# IoT_Greenhouse_V1_0_A_-_Inputs.net
KiCad netlist of a schematic drawn in Altium Designer
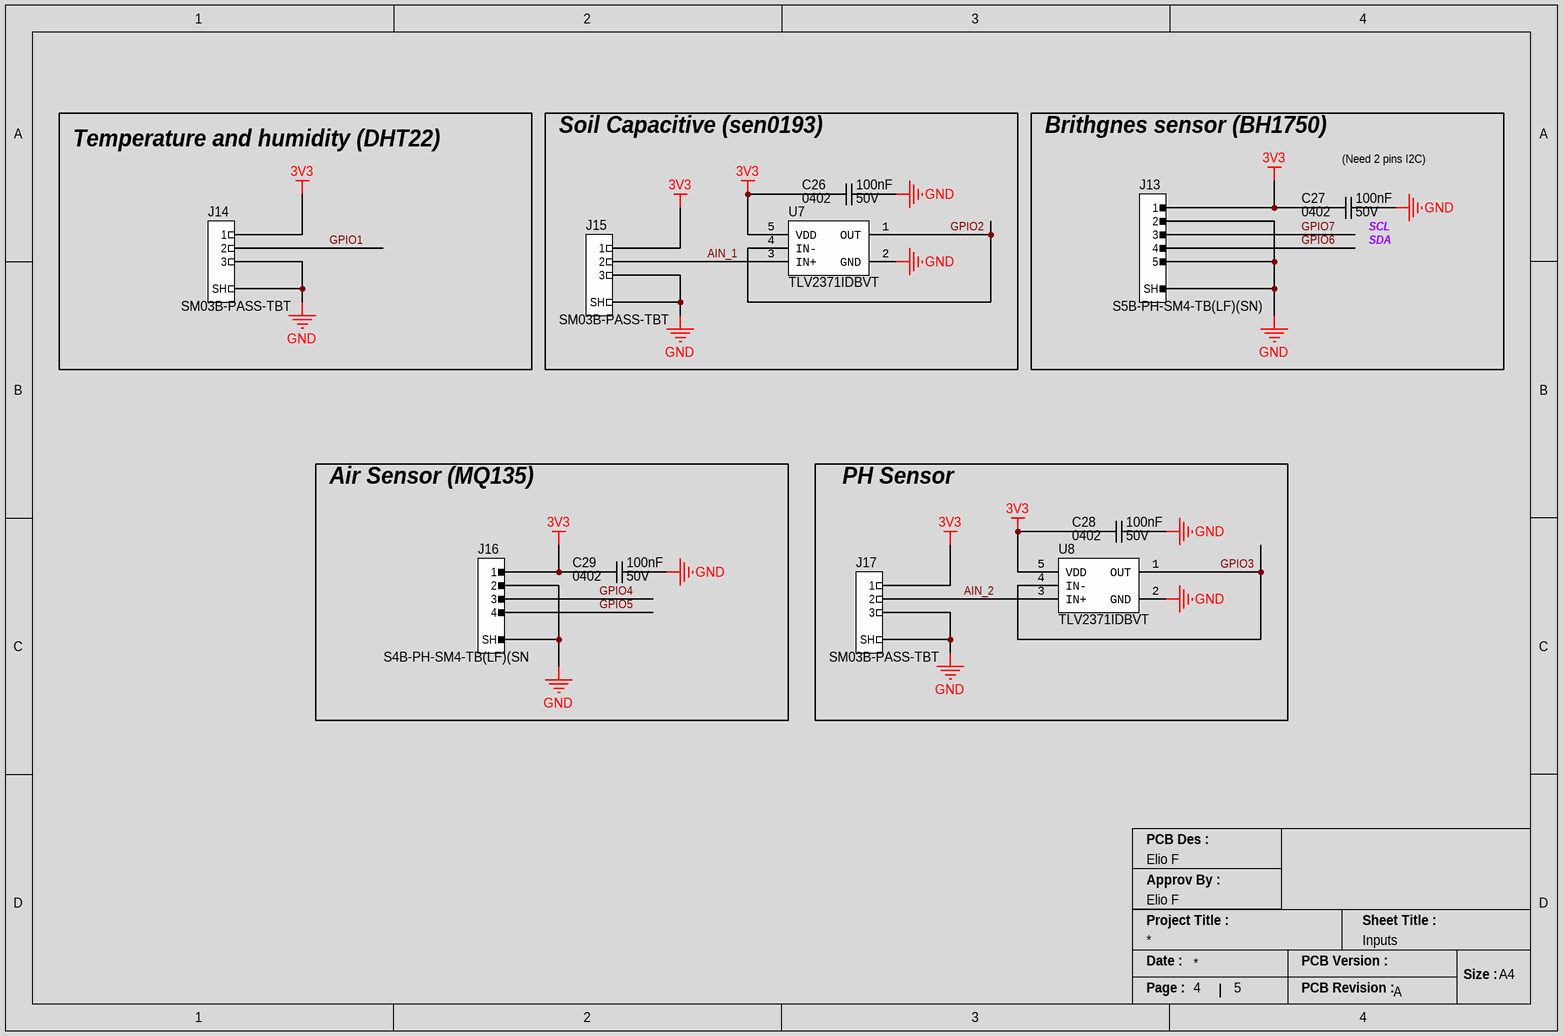
[diagram p0: IoT_Greenhouse V1.0 A - Inputs.SchDoc]

(export (version "E")
  (design (tool "Eeschema 10.0.6"))
  (components
    (comp (ref "C26")
      (value "GRM155R71H104KE14D")
      (footprint "CAP_0402_CAPC1005X05N")
      (description "Multilayer Ceramic Capacitor, 0.1 uF, 16 V, ± 10%, X7R, 0402 [1005 Metric]")
      (fields
        (field (name "MANUFACTURER") "Murata")
        (field (name "TOLERANCE") "10%")
        (field (name "VOLTAGE RATING") "50V")
        (field (name "CAPACITANCE") "100nF")
        (field (name "CASE/PACKAGE") "0402")
      )
      (libsource (lib "Electronic Devices_LIB") (part "CAP_100NF_50V_X7R_0402"))
    )
    (comp (ref "C27")
      (value "GRM155R71H104KE14D")
      (footprint "CAP_0402_CAPC1005X05N")
      (description "Multilayer Ceramic Capacitor, 0.1 uF, 16 V, ± 10%, X7R, 0402 [1005 Metric]")
      (fields
        (field (name "MANUFACTURER") "Murata")
        (field (name "TOLERANCE") "10%")
        (field (name "VOLTAGE RATING") "50V")
        (field (name "CAPACITANCE") "100nF")
        (field (name "CASE/PACKAGE") "0402")
      )
      (libsource (lib "Electronic Devices_LIB") (part "CAP_100NF_50V_X7R_0402"))
    )
    (comp (ref "C28")
      (value "GRM155R71H104KE14D")
      (footprint "CAP_0402_CAPC1005X05N")
      (description "Multilayer Ceramic Capacitor, 0.1 uF, 16 V, ± 10%, X7R, 0402 [1005 Metric]")
      (fields
        (field (name "MANUFACTURER") "Murata")
        (field (name "TOLERANCE") "10%")
        (field (name "VOLTAGE RATING") "50V")
        (field (name "CAPACITANCE") "100nF")
        (field (name "CASE/PACKAGE") "0402")
      )
      (libsource (lib "Electronic Devices_LIB") (part "CAP_100NF_50V_X7R_0402"))
    )
    (comp (ref "C29")
      (value "GRM155R71H104KE14D")
      (footprint "CAP_0402_CAPC1005X05N")
      (description "Multilayer Ceramic Capacitor, 0.1 uF, 16 V, ± 10%, X7R, 0402 [1005 Metric]")
      (fields
        (field (name "MANUFACTURER") "Murata")
        (field (name "TOLERANCE") "10%")
        (field (name "VOLTAGE RATING") "50V")
        (field (name "CAPACITANCE") "100nF")
        (field (name "CASE/PACKAGE") "0402")
      )
      (libsource (lib "Electronic Devices_LIB") (part "CAP_100NF_50V_X7R_0402"))
    )
    (comp (ref "J13")
      (value "S5B-PH-SM4-TB(LF)(SN)")
      (footprint "CONN_JST_S5B-PH-SM4-TB_LF_SN_0")
      (description "Conn Shrouded Header (4 Sides) HDR 5 POS 2mm Solder RA SMD T/R")
      (fields (field (name "MANUFACTURER") "JST"))
      (libsource (lib "Electronic Devices_LIB") (part "CONN_JST_PH_RA_5P_2mm"))
    )
    (comp (ref "J14")
      (value "SM03B-PASS-TBT")
      (footprint "CONN_JST_SM03B-PASS-TBT_LF_SN_MFG")
      (description "Conn Header SMD R/a 3POS 2MM")
      (fields (field (name "MANUFACTURER") "JST"))
      (libsource (lib "Electronic Devices_LIB") (part "CONN_JST_PH_3P_2MM_SM03B-PASS-TBT"))
    )
    (comp (ref "J15")
      (value "SM03B-PASS-TBT")
      (footprint "CONN_JST_SM03B-PASS-TBT_LF_SN_MFG")
      (description "Conn Header SMD R/a 3POS 2MM")
      (fields (field (name "MANUFACTURER") "JST"))
      (libsource (lib "Electronic Devices_LIB") (part "CONN_JST_PH_3P_2MM_SM03B-PASS-TBT"))
    )
    (comp (ref "J16")
      (value "S4B-PH-SM4-TB(LF)(SN")
      (footprint "CONN_JST_S4B-PH-SM4-TB_LF_SN_0")
      (fields (field (name "MANUFACTURER") "JST") (field (name "JLCPCB PART NUMBER") "C265102"))
      (libsource (lib "Electronic Devices_LIB") (part "CONN_JST_PH_RA_4P_2mm_JLCPCB"))
    )
    (comp (ref "J17")
      (value "SM03B-PASS-TBT")
      (footprint "CONN_JST_SM03B-PASS-TBT_LF_SN_MFG")
      (description "Conn Header SMD R/a 3POS 2MM")
      (fields (field (name "MANUFACTURER") "JST"))
      (libsource (lib "Electronic Devices_LIB") (part "CONN_JST_PH_3P_2MM_SM03B-PASS-TBT"))
    )
    (comp (ref "U7")
      (value "TLV2371IDBVT")
      (footprint "IC_AMP_OP_SOT95P280X145-5N")
      (description "Single 550-uA/channel, 3MHz, RRIO op amp 5-SOT-23 -40 to 125")
      (fields (field (name "MANUFACTURER") "Texas Instruments"))
      (libsource (lib "Electronic Devices_LIB") (part "IC_AMP_OP_TLV2371IDBVT"))
    )
    (comp (ref "U8")
      (value "TLV2371IDBVT")
      (footprint "IC_AMP_OP_SOT95P280X145-5N")
      (description "Single 550-uA/channel, 3MHz, RRIO op amp 5-SOT-23 -40 to 125")
      (fields (field (name "MANUFACTURER") "Texas Instruments"))
      (libsource (lib "Electronic Devices_LIB") (part "IC_AMP_OP_TLV2371IDBVT"))
    )
  )
  (nets
    (net (code "1") (name "/AIN_1") (class "Default")
      (node (ref "J15") (pin "2") (pinfunction "2_2") (pintype "passive"))
      (node (ref "U7") (pin "3") (pinfunction "IN+_3") (pintype "passive"))
    )
    (net (code "2") (name "/AIN_2") (class "Default")
      (node (ref "J17") (pin "2") (pinfunction "2_2") (pintype "passive"))
      (node (ref "U8") (pin "3") (pinfunction "IN+_3") (pintype "passive"))
    )
    (net (code "3") (name "/GPIO1") (class "Default")
      (node (ref "J14") (pin "2") (pinfunction "2_2") (pintype "passive"))
    )
    (net (code "4") (name "/GPIO2") (class "Default")
      (node (ref "U7") (pin "1") (pinfunction "OUT_1") (pintype "passive"))
      (node (ref "U7") (pin "4") (pinfunction "IN-_4") (pintype "passive"))
    )
    (net (code "5") (name "/GPIO3") (class "Default")
      (node (ref "U8") (pin "1") (pinfunction "OUT_1") (pintype "passive"))
      (node (ref "U8") (pin "4") (pinfunction "IN-_4") (pintype "passive"))
    )
    (net (code "6") (name "/GPIO4") (class "Default")
      (node (ref "J16") (pin "3") (pinfunction "3_3") (pintype "passive"))
    )
    (net (code "7") (name "/GPIO5") (class "Default")
      (node (ref "J16") (pin "4") (pinfunction "4_4") (pintype "passive"))
    )
    (net (code "8") (name "/GPIO6") (class "Default")
      (node (ref "J13") (pin "4") (pinfunction "4_4") (pintype "passive"))
    )
    (net (code "9") (name "/GPIO7") (class "Default")
      (node (ref "J13") (pin "3") (pinfunction "3_3") (pintype "passive"))
    )
    (net (code "10") (name "3V3") (class "Default")
      (node (ref "C26") (pin "2") (pinfunction "2_2") (pintype "passive"))
      (node (ref "C27") (pin "2") (pinfunction "2_2") (pintype "passive"))
      (node (ref "C28") (pin "2") (pinfunction "2_2") (pintype "passive"))
      (node (ref "C29") (pin "2") (pinfunction "2_2") (pintype "passive"))
      (node (ref "J13") (pin "1") (pinfunction "1_1") (pintype "passive"))
      (node (ref "J14") (pin "1") (pinfunction "1_1") (pintype "passive"))
      (node (ref "J15") (pin "1") (pinfunction "1_1") (pintype "passive"))
      (node (ref "J16") (pin "1") (pinfunction "1_1") (pintype "passive"))
      (node (ref "J17") (pin "1") (pinfunction "1_1") (pintype "passive"))
      (node (ref "U7") (pin "5") (pinfunction "VDD_5") (pintype "power_in"))
      (node (ref "U8") (pin "5") (pinfunction "VDD_5") (pintype "power_in"))
    )
    (net (code "11") (name "GND") (class "Default")
      (node (ref "C26") (pin "1") (pinfunction "1_1") (pintype "passive"))
      (node (ref "C27") (pin "1") (pinfunction "1_1") (pintype "passive"))
      (node (ref "C28") (pin "1") (pinfunction "1_1") (pintype "passive"))
      (node (ref "C29") (pin "1") (pinfunction "1_1") (pintype "passive"))
      (node (ref "J13") (pin "0") (pinfunction "SH_0") (pintype "passive"))
      (node (ref "J13") (pin "2") (pinfunction "2_2") (pintype "passive"))
      (node (ref "J13") (pin "5") (pinfunction "5_5") (pintype "passive"))
      (node (ref "J14") (pin "3") (pinfunction "3_3") (pintype "passive"))
      (node (ref "J14") (pin "SH") (pinfunction "SH_SH") (pintype "passive"))
      (node (ref "J15") (pin "3") (pinfunction "3_3") (pintype "passive"))
      (node (ref "J15") (pin "SH") (pinfunction "SH_SH") (pintype "passive"))
      (node (ref "J16") (pin "0") (pinfunction "SH_0") (pintype "passive"))
      (node (ref "J16") (pin "2") (pinfunction "2_2") (pintype "passive"))
      (node (ref "J17") (pin "3") (pinfunction "3_3") (pintype "passive"))
      (node (ref "J17") (pin "SH") (pinfunction "SH_SH") (pintype "passive"))
      (node (ref "U7") (pin "2") (pinfunction "GND_2") (pintype "power_in"))
      (node (ref "U8") (pin "2") (pinfunction "GND_2") (pintype "power_in"))
    )
  )
)
